# nRF.net
KiCad netlist of a schematic drawn in Altium Designer
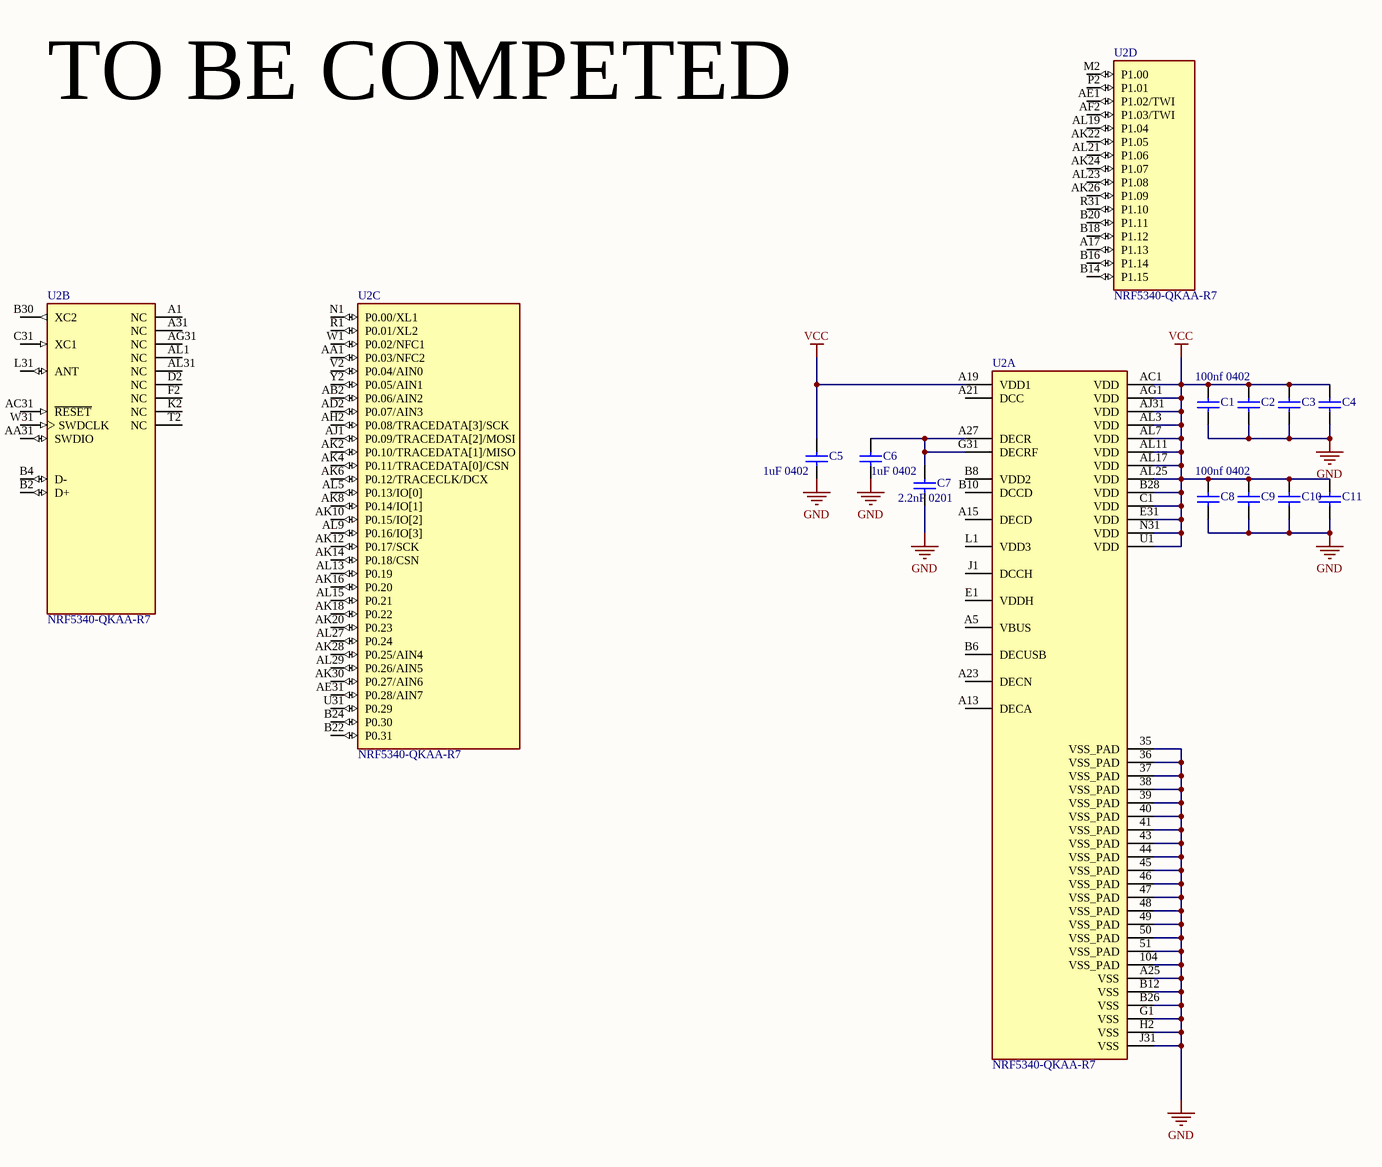
[diagram p0: nRF.SchDoc]

(export (version "E")
  (design (tool "Eeschema 10.0.6"))
  (components
    (comp (ref "C1")
      (value "100nf 0402")
      (description "Capacitor")
      (fields (field (name "PUBLISHER") "Altium Limited"))
      (libsource (lib "Other") (part "100nf 0402"))
    )
    (comp (ref "C2")
      (value "100nf 0402")
      (description "Capacitor")
      (fields (field (name "PUBLISHER") "Altium Limited"))
      (libsource (lib "Other") (part "100nf 0402"))
    )
    (comp (ref "C3")
      (value "100nf 0402")
      (description "Capacitor")
      (fields (field (name "PUBLISHER") "Altium Limited"))
      (libsource (lib "Other") (part "100nf 0402"))
    )
    (comp (ref "C4")
      (value "100nf 0402")
      (description "Capacitor")
      (fields (field (name "PUBLISHER") "Altium Limited"))
      (libsource (lib "Other") (part "100nf 0402"))
    )
    (comp (ref "C5")
      (value "1uF 0402")
      (description "Capacitor")
      (fields (field (name "PUBLISHER") "Altium Limited"))
      (libsource (lib "Other") (part "1uF 0402"))
    )
    (comp (ref "C6")
      (value "1uF 0402")
      (description "Capacitor")
      (fields (field (name "PUBLISHER") "Altium Limited"))
      (libsource (lib "Other") (part "1uF 0402"))
    )
    (comp (ref "C7")
      (value "2.2nF 0201")
      (description "Capacitor")
      (fields (field (name "PUBLISHER") "Altium Limited"))
      (libsource (lib "Other") (part "2.2nF 0201"))
    )
    (comp (ref "C8")
      (value "100nf 0402")
      (description "Capacitor")
      (fields (field (name "PUBLISHER") "Altium Limited"))
      (libsource (lib "Other") (part "100nf 0402"))
    )
    (comp (ref "C9")
      (value "100nf 0402")
      (description "Capacitor")
      (fields (field (name "PUBLISHER") "Altium Limited"))
      (libsource (lib "Other") (part "100nf 0402"))
    )
    (comp (ref "C10")
      (value "100nf 0402")
      (description "Capacitor")
      (fields (field (name "PUBLISHER") "Altium Limited"))
      (libsource (lib "Other") (part "100nf 0402"))
    )
    (comp (ref "C11")
      (value "100nf 0402")
      (description "Capacitor")
      (fields (field (name "PUBLISHER") "Altium Limited"))
      (libsource (lib "Other") (part "100nf 0402"))
    )
    (comp (ref "U2")
      (value "NRF5340-QKAA-R7")
      (footprint "XCVR_NRF5340-QKAA-R7")
      (fields (field (name "MF") "Nordic Semiconductor ASA"))
      (libsource (lib "NRF5340-QKAA-R7") (part "NRF5340-QKAA-R7"))
    )
  )
  (nets
    (net (code "1") (name "GND") (class "Default")
      (node (ref "C1") (pin "1") (pinfunction "1_1") (pintype "passive"))
      (node (ref "C10") (pin "1") (pinfunction "1_1") (pintype "passive"))
      (node (ref "C11") (pin "1") (pinfunction "1_1") (pintype "passive"))
      (node (ref "C2") (pin "1") (pinfunction "1_1") (pintype "passive"))
      (node (ref "C3") (pin "1") (pinfunction "1_1") (pintype "passive"))
      (node (ref "C4") (pin "1") (pinfunction "1_1") (pintype "passive"))
      (node (ref "C5") (pin "1") (pinfunction "1_1") (pintype "passive"))
      (node (ref "C6") (pin "1") (pinfunction "1_1") (pintype "passive"))
      (node (ref "C7") (pin "1") (pinfunction "1_1") (pintype "passive"))
      (node (ref "C8") (pin "1") (pinfunction "1_1") (pintype "passive"))
      (node (ref "C9") (pin "1") (pinfunction "1_1") (pintype "passive"))
      (node (ref "U2") (pin "104") (pinfunction "VSS_PAD_104") (pintype "power_in"))
      (node (ref "U2") (pin "35") (pinfunction "VSS_PAD_35") (pintype "power_in"))
      (node (ref "U2") (pin "36") (pinfunction "VSS_PAD_36") (pintype "power_in"))
      (node (ref "U2") (pin "37") (pinfunction "VSS_PAD_37") (pintype "power_in"))
      (node (ref "U2") (pin "38") (pinfunction "VSS_PAD_38") (pintype "power_in"))
      (node (ref "U2") (pin "39") (pinfunction "VSS_PAD_39") (pintype "power_in"))
      (node (ref "U2") (pin "40") (pinfunction "VSS_PAD_40") (pintype "power_in"))
      (node (ref "U2") (pin "41") (pinfunction "VSS_PAD_41") (pintype "power_in"))
      (node (ref "U2") (pin "43") (pinfunction "VSS_PAD_43") (pintype "power_in"))
      (node (ref "U2") (pin "44") (pinfunction "VSS_PAD_44") (pintype "power_in"))
      (node (ref "U2") (pin "45") (pinfunction "VSS_PAD_45") (pintype "power_in"))
      (node (ref "U2") (pin "46") (pinfunction "VSS_PAD_46") (pintype "power_in"))
      (node (ref "U2") (pin "47") (pinfunction "VSS_PAD_47") (pintype "power_in"))
      (node (ref "U2") (pin "48") (pinfunction "VSS_PAD_48") (pintype "power_in"))
      (node (ref "U2") (pin "49") (pinfunction "VSS_PAD_49") (pintype "power_in"))
      (node (ref "U2") (pin "50") (pinfunction "VSS_PAD_50") (pintype "power_in"))
      (node (ref "U2") (pin "51") (pinfunction "VSS_PAD_51") (pintype "power_in"))
      (node (ref "U2") (pin "A25") (pinfunction "VSS_A25") (pintype "power_in"))
      (node (ref "U2") (pin "B12") (pinfunction "VSS_B12") (pintype "power_in"))
      (node (ref "U2") (pin "B26") (pinfunction "VSS_B26") (pintype "power_in"))
      (node (ref "U2") (pin "G1") (pinfunction "VSS_G1") (pintype "power_in"))
      (node (ref "U2") (pin "H2") (pinfunction "VSS_H2") (pintype "power_in"))
      (node (ref "U2") (pin "J31") (pinfunction "VSS_J31") (pintype "power_in"))
    )
    (net (code "2") (name "Net-(U2A-DECR)") (class "Default")
      (node (ref "C6") (pin "2") (pinfunction "2_2") (pintype "passive"))
      (node (ref "C7") (pin "2") (pinfunction "2_2") (pintype "passive"))
      (node (ref "U2") (pin "A27") (pinfunction "DECR_A27") (pintype "power_in"))
      (node (ref "U2") (pin "G31") (pinfunction "DECRF_G31") (pintype "power_in"))
    )
    (net (code "3") (name "VCC") (class "Default")
      (node (ref "C1") (pin "2") (pinfunction "2_2") (pintype "passive"))
      (node (ref "C10") (pin "2") (pinfunction "2_2") (pintype "passive"))
      (node (ref "C11") (pin "2") (pinfunction "2_2") (pintype "passive"))
      (node (ref "C2") (pin "2") (pinfunction "2_2") (pintype "passive"))
      (node (ref "C3") (pin "2") (pinfunction "2_2") (pintype "passive"))
      (node (ref "C4") (pin "2") (pinfunction "2_2") (pintype "passive"))
      (node (ref "C5") (pin "2") (pinfunction "2_2") (pintype "passive"))
      (node (ref "C8") (pin "2") (pinfunction "2_2") (pintype "passive"))
      (node (ref "C9") (pin "2") (pinfunction "2_2") (pintype "passive"))
      (node (ref "U2") (pin "A19") (pinfunction "VDD1_A19") (pintype "power_in"))
      (node (ref "U2") (pin "AC1") (pinfunction "VDD_AC1") (pintype "power_in"))
      (node (ref "U2") (pin "AG1") (pinfunction "VDD_AG1") (pintype "power_in"))
      (node (ref "U2") (pin "AJ31") (pinfunction "VDD_AJ31") (pintype "power_in"))
      (node (ref "U2") (pin "AL11") (pinfunction "VDD_AL11") (pintype "power_in"))
      (node (ref "U2") (pin "AL17") (pinfunction "VDD_AL17") (pintype "power_in"))
      (node (ref "U2") (pin "AL25") (pinfunction "VDD_AL25") (pintype "power_in"))
      (node (ref "U2") (pin "AL3") (pinfunction "VDD_AL3") (pintype "power_in"))
      (node (ref "U2") (pin "AL7") (pinfunction "VDD_AL7") (pintype "power_in"))
      (node (ref "U2") (pin "B28") (pinfunction "VDD_B28") (pintype "power_in"))
      (node (ref "U2") (pin "C1") (pinfunction "VDD_C1") (pintype "power_in"))
      (node (ref "U2") (pin "E31") (pinfunction "VDD_E31") (pintype "power_in"))
      (node (ref "U2") (pin "N31") (pinfunction "VDD_N31") (pintype "power_in"))
      (node (ref "U2") (pin "U1") (pinfunction "VDD_U1") (pintype "power_in"))
    )
    (net (code "4") (name "unconnected-(U2A-DCC-PadA21)") (class "Default")
      (node (ref "U2") (pin "A21") (pinfunction "DCC_A21") (pintype "power_in"))
    )
    (net (code "5") (name "unconnected-(U2A-DCCD-PadB10)") (class "Default")
      (node (ref "U2") (pin "B10") (pinfunction "DCCD_B10") (pintype "power_in"))
    )
    (net (code "6") (name "unconnected-(U2A-DCCH-PadJ1)") (class "Default")
      (node (ref "U2") (pin "J1") (pinfunction "DCCH_J1") (pintype "power_in"))
    )
    (net (code "7") (name "unconnected-(U2A-DECA-PadA13)") (class "Default")
      (node (ref "U2") (pin "A13") (pinfunction "DECA_A13") (pintype "power_in"))
    )
    (net (code "8") (name "unconnected-(U2A-DECD-PadA15)") (class "Default")
      (node (ref "U2") (pin "A15") (pinfunction "DECD_A15") (pintype "power_in"))
    )
    (net (code "9") (name "unconnected-(U2A-DECN-PadA23)") (class "Default")
      (node (ref "U2") (pin "A23") (pinfunction "DECN_A23") (pintype "power_in"))
    )
    (net (code "10") (name "unconnected-(U2A-DECUSB-PadB6)") (class "Default")
      (node (ref "U2") (pin "B6") (pinfunction "DECUSB_B6") (pintype "power_in"))
    )
    (net (code "11") (name "unconnected-(U2A-VBUS-PadA5)") (class "Default")
      (node (ref "U2") (pin "A5") (pinfunction "VBUS_A5") (pintype "power_in"))
    )
    (net (code "12") (name "unconnected-(U2A-VDD2-PadB8)") (class "Default")
      (node (ref "U2") (pin "B8") (pinfunction "VDD2_B8") (pintype "power_in"))
    )
    (net (code "13") (name "unconnected-(U2A-VDD3-PadL1)") (class "Default")
      (node (ref "U2") (pin "L1") (pinfunction "VDD3_L1") (pintype "power_in"))
    )
    (net (code "14") (name "unconnected-(U2A-VDDH-PadE1)") (class "Default")
      (node (ref "U2") (pin "E1") (pinfunction "VDDH_E1") (pintype "power_in"))
    )
    (net (code "15") (name "unconnected-(U2B-ANT-PadL31)") (class "Default")
      (node (ref "U2") (pin "L31") (pinfunction "ANT_L31") (pintype "bidirectional"))
    )
    (net (code "16") (name "unconnected-(U2B-D+-PadB2)") (class "Default")
      (node (ref "U2") (pin "B2") (pinfunction "D+_B2") (pintype "bidirectional"))
    )
    (net (code "17") (name "unconnected-(U2B-D--PadB4)") (class "Default")
      (node (ref "U2") (pin "B4") (pinfunction "D-_B4") (pintype "bidirectional"))
    )
    (net (code "18") (name "unconnected-(U2B-NC-PadA1)") (class "Default")
      (node (ref "U2") (pin "A1") (pinfunction "NC_A1") (pintype "passive"))
    )
    (net (code "19") (name "unconnected-(U2B-NC-PadA31)") (class "Default")
      (node (ref "U2") (pin "A31") (pinfunction "NC_A31") (pintype "passive"))
    )
    (net (code "20") (name "unconnected-(U2B-NC-PadAG31)") (class "Default")
      (node (ref "U2") (pin "AG31") (pinfunction "NC_AG31") (pintype "passive"))
    )
    (net (code "21") (name "unconnected-(U2B-NC-PadAL1)") (class "Default")
      (node (ref "U2") (pin "AL1") (pinfunction "NC_AL1") (pintype "passive"))
    )
    (net (code "22") (name "unconnected-(U2B-NC-PadAL31)") (class "Default")
      (node (ref "U2") (pin "AL31") (pinfunction "NC_AL31") (pintype "passive"))
    )
    (net (code "23") (name "unconnected-(U2B-NC-PadD2)") (class "Default")
      (node (ref "U2") (pin "D2") (pinfunction "NC_D2") (pintype "passive"))
    )
    (net (code "24") (name "unconnected-(U2B-NC-PadF2)") (class "Default")
      (node (ref "U2") (pin "F2") (pinfunction "NC_F2") (pintype "passive"))
    )
    (net (code "25") (name "unconnected-(U2B-NC-PadK2)") (class "Default")
      (node (ref "U2") (pin "K2") (pinfunction "NC_K2") (pintype "passive"))
    )
    (net (code "26") (name "unconnected-(U2B-NC-PadT2)") (class "Default")
      (node (ref "U2") (pin "T2") (pinfunction "NC_T2") (pintype "passive"))
    )
    (net (code "27") (name "unconnected-(U2B-SWDCLK-PadW31)") (class "Default")
      (node (ref "U2") (pin "W31") (pinfunction "SWDCLK_W31") (pintype "input"))
    )
    (net (code "28") (name "unconnected-(U2B-SWDIO-PadAA31)") (class "Default")
      (node (ref "U2") (pin "AA31") (pinfunction "SWDIO_AA31") (pintype "bidirectional"))
    )
    (net (code "29") (name "unconnected-(U2B-XC1-PadC31)") (class "Default")
      (node (ref "U2") (pin "C31") (pinfunction "XC1_C31") (pintype "input"))
    )
    (net (code "30") (name "unconnected-(U2B-XC2-PadB30)") (class "Default")
      (node (ref "U2") (pin "B30") (pinfunction "XC2_B30") (pintype "output"))
    )
    (net (code "31") (name "unconnected-(U2B-~{RESET}-PadAC31)") (class "Default")
      (node (ref "U2") (pin "AC31") (pinfunction "~{RESET}_AC31") (pintype "input"))
    )
    (net (code "32") (name "unconnected-(U2C-P0.00{slash}XL1-PadN1)") (class "Default")
      (node (ref "U2") (pin "N1") (pinfunction "P0.00/XL1_N1") (pintype "bidirectional"))
    )
    (net (code "33") (name "unconnected-(U2C-P0.01{slash}XL2-PadR1)") (class "Default")
      (node (ref "U2") (pin "R1") (pinfunction "P0.01/XL2_R1") (pintype "bidirectional"))
    )
    (net (code "34") (name "unconnected-(U2C-P0.02{slash}NFC1-PadW1)") (class "Default")
      (node (ref "U2") (pin "W1") (pinfunction "P0.02/NFC1_W1") (pintype "bidirectional"))
    )
    (net (code "35") (name "unconnected-(U2C-P0.03{slash}NFC2-PadAA1)") (class "Default")
      (node (ref "U2") (pin "AA1") (pinfunction "P0.03/NFC2_AA1") (pintype "bidirectional"))
    )
    (net (code "36") (name "unconnected-(U2C-P0.04{slash}AIN0-PadV2)") (class "Default")
      (node (ref "U2") (pin "V2") (pinfunction "P0.04/AIN0_V2") (pintype "bidirectional"))
    )
    (net (code "37") (name "unconnected-(U2C-P0.05{slash}AIN1-PadY2)") (class "Default")
      (node (ref "U2") (pin "Y2") (pinfunction "P0.05/AIN1_Y2") (pintype "bidirectional"))
    )
    (net (code "38") (name "unconnected-(U2C-P0.06{slash}AIN2-PadAB2)") (class "Default")
      (node (ref "U2") (pin "AB2") (pinfunction "P0.06/AIN2_AB2") (pintype "bidirectional"))
    )
    (net (code "39") (name "unconnected-(U2C-P0.07{slash}AIN3-PadAD2)") (class "Default")
      (node (ref "U2") (pin "AD2") (pinfunction "P0.07/AIN3_AD2") (pintype "bidirectional"))
    )
    (net (code "40") (name "unconnected-(U2C-P0.08{slash}TRACEDATA[3]{slash}SCK-PadAH2)") (class "Default")
      (node (ref "U2") (pin "AH2") (pinfunction "P0.08/TRACEDATA[3]/SCK_AH2") (pintype "bidirectional"))
    )
    (net (code "41") (name "unconnected-(U2C-P0.09{slash}TRACEDATA[2]{slash}MOSI-PadAJ1)") (class "Default")
      (node (ref "U2") (pin "AJ1") (pinfunction "P0.09/TRACEDATA[2]/MOSI_AJ1") (pintype "bidirectional"))
    )
    (net (code "42") (name "unconnected-(U2C-P0.10{slash}TRACEDATA[1]{slash}MISO-PadAK2)") (class "Default")
      (node (ref "U2") (pin "AK2") (pinfunction "P0.10/TRACEDATA[1]/MISO_AK2") (pintype "bidirectional"))
    )
    (net (code "43") (name "unconnected-(U2C-P0.11{slash}TRACEDATA[0]{slash}CSN-PadAK4)") (class "Default")
      (node (ref "U2") (pin "AK4") (pinfunction "P0.11/TRACEDATA[0]/CSN_AK4") (pintype "bidirectional"))
    )
    (net (code "44") (name "unconnected-(U2C-P0.12{slash}TRACECLK{slash}DCX-PadAK6)") (class "Default")
      (node (ref "U2") (pin "AK6") (pinfunction "P0.12/TRACECLK/DCX_AK6") (pintype "bidirectional"))
    )
    (net (code "45") (name "unconnected-(U2C-P0.13{slash}IO[0]-PadAL5)") (class "Default")
      (node (ref "U2") (pin "AL5") (pinfunction "P0.13/IO[0]_AL5") (pintype "bidirectional"))
    )
    (net (code "46") (name "unconnected-(U2C-P0.14{slash}IO[1]-PadAK8)") (class "Default")
      (node (ref "U2") (pin "AK8") (pinfunction "P0.14/IO[1]_AK8") (pintype "bidirectional"))
    )
    (net (code "47") (name "unconnected-(U2C-P0.15{slash}IO[2]-PadAK10)") (class "Default")
      (node (ref "U2") (pin "AK10") (pinfunction "P0.15/IO[2]_AK10") (pintype "bidirectional"))
    )
    (net (code "48") (name "unconnected-(U2C-P0.16{slash}IO[3]-PadAL9)") (class "Default")
      (node (ref "U2") (pin "AL9") (pinfunction "P0.16/IO[3]_AL9") (pintype "bidirectional"))
    )
    (net (code "49") (name "unconnected-(U2C-P0.17{slash}SCK-PadAK12)") (class "Default")
      (node (ref "U2") (pin "AK12") (pinfunction "P0.17/SCK_AK12") (pintype "bidirectional"))
    )
    (net (code "50") (name "unconnected-(U2C-P0.18{slash}CSN-PadAK14)") (class "Default")
      (node (ref "U2") (pin "AK14") (pinfunction "P0.18/CSN_AK14") (pintype "bidirectional"))
    )
    (net (code "51") (name "unconnected-(U2C-P0.19-PadAL13)") (class "Default")
      (node (ref "U2") (pin "AL13") (pinfunction "P0.19_AL13") (pintype "bidirectional"))
    )
    (net (code "52") (name "unconnected-(U2C-P0.20-PadAK16)") (class "Default")
      (node (ref "U2") (pin "AK16") (pinfunction "P0.20_AK16") (pintype "bidirectional"))
    )
    (net (code "53") (name "unconnected-(U2C-P0.21-PadAL15)") (class "Default")
      (node (ref "U2") (pin "AL15") (pinfunction "P0.21_AL15") (pintype "bidirectional"))
    )
    (net (code "54") (name "unconnected-(U2C-P0.22-PadAK18)") (class "Default")
      (node (ref "U2") (pin "AK18") (pinfunction "P0.22_AK18") (pintype "bidirectional"))
    )
    (net (code "55") (name "unconnected-(U2C-P0.23-PadAK20)") (class "Default")
      (node (ref "U2") (pin "AK20") (pinfunction "P0.23_AK20") (pintype "bidirectional"))
    )
    (net (code "56") (name "unconnected-(U2C-P0.24-PadAL27)") (class "Default")
      (node (ref "U2") (pin "AL27") (pinfunction "P0.24_AL27") (pintype "bidirectional"))
    )
    (net (code "57") (name "unconnected-(U2C-P0.25{slash}AIN4-PadAK28)") (class "Default")
      (node (ref "U2") (pin "AK28") (pinfunction "P0.25/AIN4_AK28") (pintype "bidirectional"))
    )
    (net (code "58") (name "unconnected-(U2C-P0.26{slash}AIN5-PadAL29)") (class "Default")
      (node (ref "U2") (pin "AL29") (pinfunction "P0.26/AIN5_AL29") (pintype "bidirectional"))
    )
    (net (code "59") (name "unconnected-(U2C-P0.27{slash}AIN6-PadAK30)") (class "Default")
      (node (ref "U2") (pin "AK30") (pinfunction "P0.27/AIN6_AK30") (pintype "bidirectional"))
    )
    (net (code "60") (name "unconnected-(U2C-P0.28{slash}AIN7-PadAE31)") (class "Default")
      (node (ref "U2") (pin "AE31") (pinfunction "P0.28/AIN7_AE31") (pintype "bidirectional"))
    )
    (net (code "61") (name "unconnected-(U2C-P0.29-PadU31)") (class "Default")
      (node (ref "U2") (pin "U31") (pinfunction "P0.29_U31") (pintype "bidirectional"))
    )
    (net (code "62") (name "unconnected-(U2C-P0.30-PadB24)") (class "Default")
      (node (ref "U2") (pin "B24") (pinfunction "P0.30_B24") (pintype "bidirectional"))
    )
    (net (code "63") (name "unconnected-(U2C-P0.31-PadB22)") (class "Default")
      (node (ref "U2") (pin "B22") (pinfunction "P0.31_B22") (pintype "bidirectional"))
    )
    (net (code "64") (name "unconnected-(U2D-P1.00-PadM2)") (class "Default")
      (node (ref "U2") (pin "M2") (pinfunction "P1.00_M2") (pintype "bidirectional"))
    )
    (net (code "65") (name "unconnected-(U2D-P1.01-PadP2)") (class "Default")
      (node (ref "U2") (pin "P2") (pinfunction "P1.01_P2") (pintype "bidirectional"))
    )
    (net (code "66") (name "unconnected-(U2D-P1.02{slash}TWI-PadAE1)") (class "Default")
      (node (ref "U2") (pin "AE1") (pinfunction "P1.02/TWI_AE1") (pintype "bidirectional"))
    )
    (net (code "67") (name "unconnected-(U2D-P1.03{slash}TWI-PadAF2)") (class "Default")
      (node (ref "U2") (pin "AF2") (pinfunction "P1.03/TWI_AF2") (pintype "bidirectional"))
    )
    (net (code "68") (name "unconnected-(U2D-P1.04-PadAL19)") (class "Default")
      (node (ref "U2") (pin "AL19") (pinfunction "P1.04_AL19") (pintype "bidirectional"))
    )
    (net (code "69") (name "unconnected-(U2D-P1.05-PadAK22)") (class "Default")
      (node (ref "U2") (pin "AK22") (pinfunction "P1.05_AK22") (pintype "bidirectional"))
    )
    (net (code "70") (name "unconnected-(U2D-P1.06-PadAL21)") (class "Default")
      (node (ref "U2") (pin "AL21") (pinfunction "P1.06_AL21") (pintype "bidirectional"))
    )
    (net (code "71") (name "unconnected-(U2D-P1.07-PadAK24)") (class "Default")
      (node (ref "U2") (pin "AK24") (pinfunction "P1.07_AK24") (pintype "bidirectional"))
    )
    (net (code "72") (name "unconnected-(U2D-P1.08-PadAL23)") (class "Default")
      (node (ref "U2") (pin "AL23") (pinfunction "P1.08_AL23") (pintype "bidirectional"))
    )
    (net (code "73") (name "unconnected-(U2D-P1.09-PadAK26)") (class "Default")
      (node (ref "U2") (pin "AK26") (pinfunction "P1.09_AK26") (pintype "bidirectional"))
    )
    (net (code "74") (name "unconnected-(U2D-P1.10-PadR31)") (class "Default")
      (node (ref "U2") (pin "R31") (pinfunction "P1.10_R31") (pintype "bidirectional"))
    )
    (net (code "75") (name "unconnected-(U2D-P1.11-PadB20)") (class "Default")
      (node (ref "U2") (pin "B20") (pinfunction "P1.11_B20") (pintype "bidirectional"))
    )
    (net (code "76") (name "unconnected-(U2D-P1.12-PadB18)") (class "Default")
      (node (ref "U2") (pin "B18") (pinfunction "P1.12_B18") (pintype "bidirectional"))
    )
    (net (code "77") (name "unconnected-(U2D-P1.13-PadA17)") (class "Default")
      (node (ref "U2") (pin "A17") (pinfunction "P1.13_A17") (pintype "bidirectional"))
    )
    (net (code "78") (name "unconnected-(U2D-P1.14-PadB16)") (class "Default")
      (node (ref "U2") (pin "B16") (pinfunction "P1.14_B16") (pintype "bidirectional"))
    )
    (net (code "79") (name "unconnected-(U2D-P1.15-PadB14)") (class "Default")
      (node (ref "U2") (pin "B14") (pinfunction "P1.15_B14") (pintype "bidirectional"))
    )
  )
)
